# Schematics.net
KiCad netlist of a schematic drawn in Altium Designer
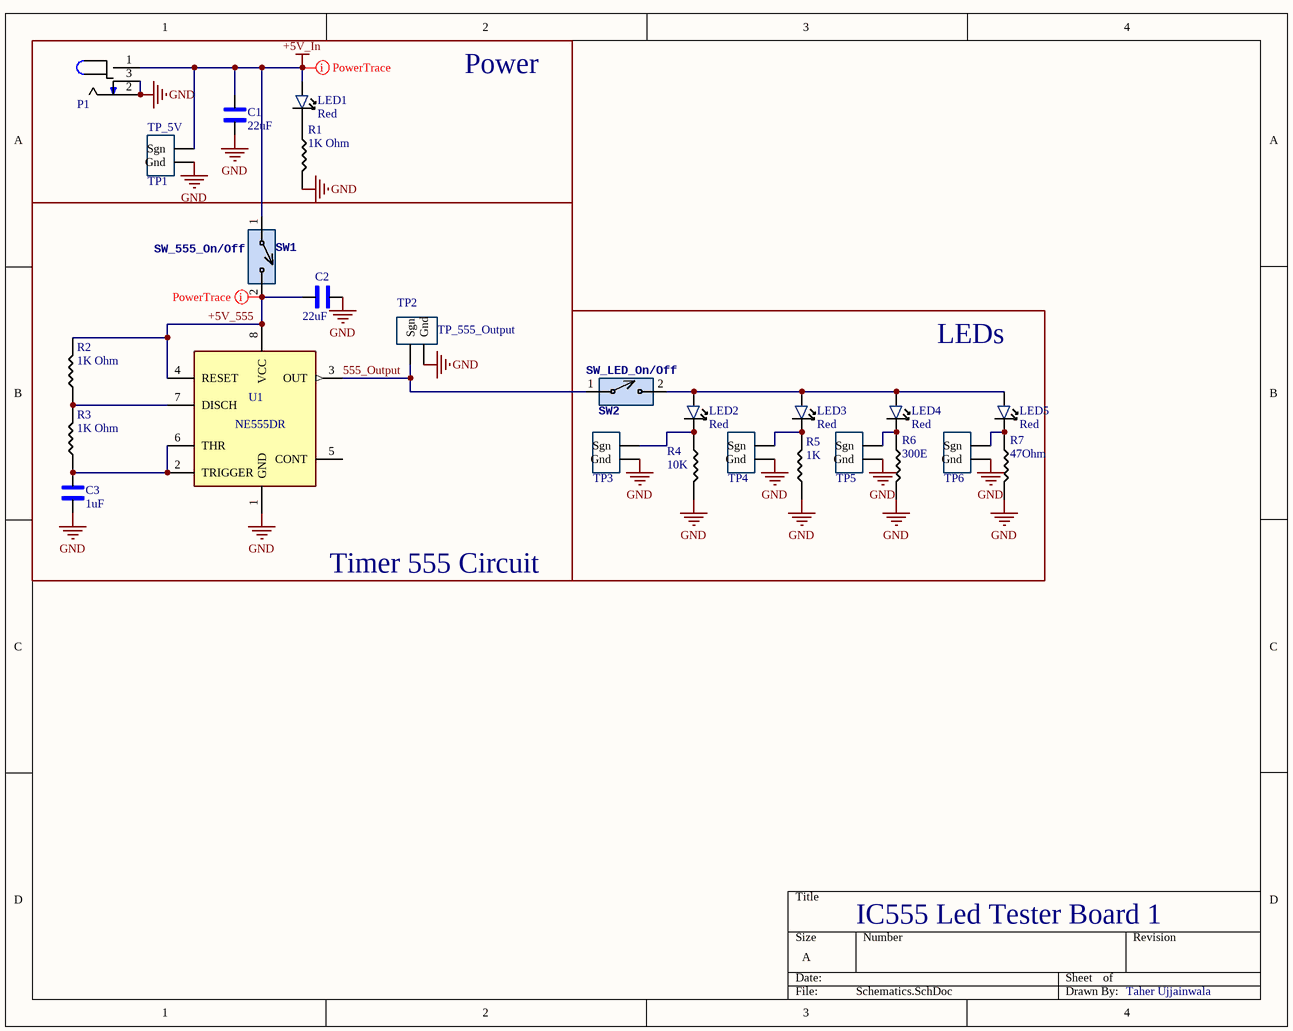
[diagram p0: Schematics.SchDoc]

(export (version "E")
  (design (tool "Eeschema 10.0.6"))
  (components
    (comp (ref "C1")
      (value "22uF")
      (footprint "1206_Passive_Capacitor")
      (description "22uF ±10% 25V X5R 1206 Multilayer Ceramic Capacitors MLCC - SMD/SMT RoHS")
      (fields (field (name "MFR PART #") "CL31A226KAHNNNE") (field (name "LCSC PART#") "C12891"))
      (libsource (lib "ECEN5730Lib_JLC_2021_08") (part "C_22uF_1206"))
    )
    (comp (ref "C2")
      (value "22uF")
      (footprint "1206_Passive_Capacitor")
      (description "22uF ±10% 25V X5R 1206 Multilayer Ceramic Capacitors MLCC - SMD/SMT RoHS")
      (fields (field (name "MFR PART #") "CL31A226KAHNNNE") (field (name "LCSC PART#") "C12891"))
      (libsource (lib "ECEN5730Lib_JLC_2021_08") (part "C_22uF_1206"))
    )
    (comp (ref "C3")
      (value "1uF")
      (footprint "1206_Passive_Capacitor")
      (description "MULTILAYER CERAMIC CAPACITORS MLCC - SMD/SMT 1UF 50V 1206 ROHS")
      (fields (field (name "DIGIKEY PART") "399-8150-1-ND") (field (name "MFR PART #") "CL31B105KBHNNNE"))
      (libsource (lib "ECEN5730Lib_JLC_2021_08") (part "C_1uF_1206"))
    )
    (comp (ref "LED1")
      (value "Red")
      (footprint "LED_1206")
      (description "Red 621~631nm 1206 Light Emitting Diodes (LED) RoHS")
      (fields (field (name "MFR PART #") "15-21/R6C-FQ1R1B/2T") (field (name "LCSC PART#") "C93133"))
      (libsource (lib "ECEN5730Lib_JLC_2021_08") (part "LED_RED_1206"))
    )
    (comp (ref "LED2")
      (value "Red")
      (footprint "LED_1206")
      (description "Red 621~631nm 1206 Light Emitting Diodes (LED) RoHS")
      (fields (field (name "MFR PART #") "15-21/R6C-FQ1R1B/2T") (field (name "LCSC PART#") "C93133"))
      (libsource (lib "ECEN5730Lib_JLC_2021_08") (part "LED_RED_1206"))
    )
    (comp (ref "LED3")
      (value "Red")
      (footprint "LED_1206")
      (description "Red 621~631nm 1206 Light Emitting Diodes (LED) RoHS")
      (fields (field (name "MFR PART #") "15-21/R6C-FQ1R1B/2T") (field (name "LCSC PART#") "C93133"))
      (libsource (lib "ECEN5730Lib_JLC_2021_08") (part "LED_RED_1206"))
    )
    (comp (ref "LED4")
      (value "Red")
      (footprint "LED_1206")
      (description "Red 621~631nm 1206 Light Emitting Diodes (LED) RoHS")
      (fields (field (name "MFR PART #") "15-21/R6C-FQ1R1B/2T") (field (name "LCSC PART#") "C93133"))
      (libsource (lib "ECEN5730Lib_JLC_2021_08") (part "LED_RED_1206"))
    )
    (comp (ref "LED5")
      (value "Red")
      (footprint "LED_1206")
      (description "Red 621~631nm 1206 Light Emitting Diodes (LED) RoHS")
      (fields (field (name "MFR PART #") "15-21/R6C-FQ1R1B/2T") (field (name "LCSC PART#") "C93133"))
      (libsource (lib "ECEN5730Lib_JLC_2021_08") (part "LED_RED_1206"))
    )
    (comp (ref "P1")
      (value "Power Jack")
      (footprint "Power_Jack")
      (description "Power Barrel Connector Jack 2.10mm ID (0.083\"), 5.50mm OD (0.217\") Through Hole, Right Angle")
      (fields (field (name "DIGIKEY PART") "CP-102A-ND") (field (name "LCSC PART#") "C136744"))
      (libsource (lib "ECEN5730Lib_JLC_2021_08") (part "P_Power Jack"))
    )
    (comp (ref "R1")
      (value "1K Ohm")
      (footprint "1206_Passive_Resitor")
      (description "CHIP RESISTOR - SURFACE MOUNT 1KOHMS ±1% 1/4W 1206 ROHS")
      (fields (field (name "DIGIKEY PART") "RNCP1206FTD1K00CT-ND") (field (name "LCSC PART#") "C4410"))
      (libsource (lib "ECEN5730Lib_JLC_2021_08") (part "R_1K_1206"))
    )
    (comp (ref "R2")
      (value "1K Ohm")
      (footprint "1206_Passive_Resitor")
      (description "CHIP RESISTOR - SURFACE MOUNT 1KOHMS ±1% 1/4W 1206 ROHS")
      (fields (field (name "DIGIKEY PART") "RNCP1206FTD1K00CT-ND") (field (name "LCSC PART#") "C4410"))
      (libsource (lib "ECEN5730Lib_JLC_2021_08") (part "R_1K_1206"))
    )
    (comp (ref "R3")
      (value "1K Ohm")
      (footprint "1206_Passive_Resitor")
      (description "CHIP RESISTOR - SURFACE MOUNT 1KOHMS ±1% 1/4W 1206 ROHS")
      (fields (field (name "DIGIKEY PART") "RNCP1206FTD1K00CT-ND") (field (name "LCSC PART#") "C4410"))
      (libsource (lib "ECEN5730Lib_JLC_2021_08") (part "R_1K_1206"))
    )
    (comp (ref "R4")
      (value "10K")
      (footprint "1206_Passive_Resitor")
      (description "10 kOhms ±5% 0.25W, 1/4W Chip Resistor 1206 (3216 Metric) Automotive AEC-Q200 Thick Film")
      (fields (field (name "DIGIKEY PART") "RMCF1206JT300RCT-ND") (field (name "LCSC PART#") "C17902"))
      (libsource (lib "ECEN5730Lib_JLC_2021_08") (part "R_10KOhm_1206"))
    )
    (comp (ref "R5")
      (value "1K")
      (footprint "1206_Passive_Resitor")
      (description "CHIP RESISTOR - SURFACE MOUNT 1KOHMS ±1% 1/4W 1206 ROHS")
      (fields (field (name "DIGIKEY PART") "RNCP1206FTD1K00CT-ND") (field (name "LCSC PART#") "C4410"))
      (libsource (lib "ECEN5730Lib_JLC_2021_08") (part "R_1K_1206"))
    )
    (comp (ref "R6")
      (value "300E")
      (footprint "1206_Passive_Resitor")
      (description "CHIP RESISTOR - SURFACE MOUNT 300OHMS ±1% 1/4W 1206 ROHS")
      (fields (field (name "MFR PART #") "1206W4F3000T5E") (field (name "LCSC PART#") "C17887"))
      (libsource (lib "ECEN5730Lib_JLC_2021_08") (part "R_300Ohm_1206"))
    )
    (comp (ref "R7")
      (value "47Ohm")
      (footprint "1206_Passive_Resitor")
      (description "47Ω ±5% 0.25W ±200ppm/℃ 1206 Chip Resistor - Surface Mount RoHS")
      (fields (field (name "MFR PART #") "1206W4J0470T5E") (field (name "LCSC PART#") "C25384"))
      (libsource (lib "ECEN5730Lib_JLC_2021_08") (part "R_47Ohm_1206"))
    )
    (comp (ref "SW1")
      (value "SW_555_On/Off")
      (footprint "2Pin-Header-Conn")
      (description "2Pin Header")
      (fields (field (name "LCSC PART#") "C124375"))
      (libsource (lib "ECEN5730Lib_JLC_2021_08") (part "SW_2Pin_100mil_Switch"))
    )
    (comp (ref "SW2")
      (value "SW_LED_On/Off")
      (footprint "2Pin-Header-Conn")
      (description "2Pin Header")
      (fields (field (name "LCSC PART#") "C124375"))
      (libsource (lib "") (part "SW_2Pin_100mil_Switch_1"))
    )
    (comp (ref "TP1")
      (value "TP_5V")
      (footprint "TP10x_Probe")
      (description "Test Point 300 mil centers")
      (libsource (lib "ECEN5730Lib_Manual_2021_08") (part "TP_10x_Probe"))
    )
    (comp (ref "TP2")
      (value "TP_555_Output")
      (footprint "TP10x_Probe")
      (description "Test Point 300 mil centers")
      (libsource (lib "") (part "TP_10x_Probe_1"))
    )
    (comp (ref "TP3")
      (value "10x Probe TP")
      (footprint "TP10x_Probe")
      (description "Test Point 300 mil centers")
      (libsource (lib "ECEN5730Lib_Manual_2021_08") (part "TP_10x_Probe"))
    )
    (comp (ref "TP4")
      (value "10x Probe TP")
      (footprint "TP10x_Probe")
      (description "Test Point 300 mil centers")
      (libsource (lib "ECEN5730Lib_Manual_2021_08") (part "TP_10x_Probe"))
    )
    (comp (ref "TP5")
      (value "10x Probe TP")
      (footprint "TP10x_Probe")
      (description "Test Point 300 mil centers")
      (libsource (lib "ECEN5730Lib_Manual_2021_08") (part "TP_10x_Probe"))
    )
    (comp (ref "TP6")
      (value "10x Probe TP")
      (footprint "TP10x_Probe")
      (description "Test Point 300 mil centers")
      (libsource (lib "ECEN5730Lib_Manual_2021_08") (part "TP_10x_Probe"))
    )
    (comp (ref "U1")
      (value "NE555DR")
      (footprint "TS555IDTTR")
      (description "555 Timer SOIC-8_150MIL ROHS 150ns Rise Time")
      (fields (field (name "LCSC PART#") "C7593"))
      (libsource (lib "ECEN5730Lib_JLC_2021_08") (part "U_555_Slow"))
    )
  )
  (nets
    (net (code "1") (name "+5V_In") (class "Default")
      (node (ref "C1") (pin "2") (pinfunction "2_2") (pintype "passive"))
      (node (ref "LED1") (pin "1") (pinfunction "1_1") (pintype "passive"))
      (node (ref "P1") (pin "1") (pinfunction "1_1") (pintype "power_in"))
      (node (ref "SW1") (pin "1") (pinfunction "1_1") (pintype "passive"))
      (node (ref "TP1") (pin "1") (pinfunction "Sgn_1") (pintype "passive"))
    )
    (net (code "2") (name "/+5V_555") (class "Default")
      (node (ref "C2") (pin "2") (pinfunction "2_2") (pintype "passive"))
      (node (ref "R2") (pin "2") (pinfunction "2_2") (pintype "passive"))
      (node (ref "SW1") (pin "2") (pinfunction "2_2") (pintype "passive"))
      (node (ref "U1") (pin "4") (pinfunction "RESET_4") (pintype "passive"))
      (node (ref "U1") (pin "8") (pinfunction "VCC_8") (pintype "power_in"))
    )
    (net (code "3") (name "/555_Output") (class "Default")
      (node (ref "SW2") (pin "1") (pinfunction "1_1") (pintype "passive"))
      (node (ref "TP2") (pin "1") (pinfunction "Sgn_1") (pintype "passive"))
      (node (ref "U1") (pin "3") (pinfunction "OUT_3") (pintype "output"))
    )
    (net (code "4") (name "GND") (class "Default")
      (node (ref "C1") (pin "1") (pinfunction "1_1") (pintype "passive"))
      (node (ref "C2") (pin "1") (pinfunction "1_1") (pintype "passive"))
      (node (ref "C3") (pin "1") (pinfunction "1_1") (pintype "passive"))
      (node (ref "P1") (pin "2") (pinfunction "2_2") (pintype "power_in"))
      (node (ref "P1") (pin "3") (pinfunction "3_3") (pintype "power_in"))
      (node (ref "R1") (pin "2") (pinfunction "2_2") (pintype "passive"))
      (node (ref "R4") (pin "2") (pinfunction "2_2") (pintype "passive"))
      (node (ref "R5") (pin "1") (pinfunction "1_1") (pintype "passive"))
      (node (ref "R6") (pin "2") (pinfunction "2_2") (pintype "passive"))
      (node (ref "R7") (pin "2") (pinfunction "2_2") (pintype "passive"))
      (node (ref "TP1") (pin "2") (pinfunction "Gnd_2") (pintype "passive"))
      (node (ref "TP2") (pin "2") (pinfunction "Gnd_2") (pintype "passive"))
      (node (ref "TP3") (pin "2") (pinfunction "Gnd_2") (pintype "passive"))
      (node (ref "TP4") (pin "2") (pinfunction "Gnd_2") (pintype "passive"))
      (node (ref "TP5") (pin "2") (pinfunction "Gnd_2") (pintype "passive"))
      (node (ref "TP6") (pin "2") (pinfunction "Gnd_2") (pintype "passive"))
      (node (ref "U1") (pin "1") (pinfunction "GND_1") (pintype "power_in"))
    )
    (net (code "5") (name "Net-(LED1-Pad2)") (class "Default")
      (node (ref "LED1") (pin "2") (pinfunction "2_2") (pintype "passive"))
      (node (ref "R1") (pin "1") (pinfunction "1_1") (pintype "passive"))
    )
    (net (code "6") (name "Net-(LED2-Pad1)") (class "Default")
      (node (ref "LED2") (pin "1") (pinfunction "1_1") (pintype "passive"))
      (node (ref "LED3") (pin "1") (pinfunction "1_1") (pintype "passive"))
      (node (ref "LED4") (pin "1") (pinfunction "1_1") (pintype "passive"))
      (node (ref "LED5") (pin "1") (pinfunction "1_1") (pintype "passive"))
      (node (ref "SW2") (pin "2") (pinfunction "2_2") (pintype "passive"))
    )
    (net (code "7") (name "Net-(TP3-Sgn)") (class "Default")
      (node (ref "LED2") (pin "2") (pinfunction "2_2") (pintype "passive"))
      (node (ref "R4") (pin "1") (pinfunction "1_1") (pintype "passive"))
      (node (ref "TP3") (pin "1") (pinfunction "Sgn_1") (pintype "passive"))
    )
    (net (code "8") (name "Net-(TP4-Sgn)") (class "Default")
      (node (ref "LED3") (pin "2") (pinfunction "2_2") (pintype "passive"))
      (node (ref "R5") (pin "2") (pinfunction "2_2") (pintype "passive"))
      (node (ref "TP4") (pin "1") (pinfunction "Sgn_1") (pintype "passive"))
    )
    (net (code "9") (name "Net-(TP5-Sgn)") (class "Default")
      (node (ref "LED4") (pin "2") (pinfunction "2_2") (pintype "passive"))
      (node (ref "R6") (pin "1") (pinfunction "1_1") (pintype "passive"))
      (node (ref "TP5") (pin "1") (pinfunction "Sgn_1") (pintype "passive"))
    )
    (net (code "10") (name "Net-(TP6-Sgn)") (class "Default")
      (node (ref "LED5") (pin "2") (pinfunction "2_2") (pintype "passive"))
      (node (ref "R7") (pin "1") (pinfunction "1_1") (pintype "passive"))
      (node (ref "TP6") (pin "1") (pinfunction "Sgn_1") (pintype "passive"))
    )
    (net (code "11") (name "Net-(U1-DISCH)") (class "Default")
      (node (ref "R2") (pin "1") (pinfunction "1_1") (pintype "passive"))
      (node (ref "R3") (pin "2") (pinfunction "2_2") (pintype "passive"))
      (node (ref "U1") (pin "7") (pinfunction "DISCH_7") (pintype "passive"))
    )
    (net (code "12") (name "Net-(U1-THR)") (class "Default")
      (node (ref "C3") (pin "2") (pinfunction "2_2") (pintype "passive"))
      (node (ref "R3") (pin "1") (pinfunction "1_1") (pintype "passive"))
      (node (ref "U1") (pin "2") (pinfunction "TRIGGER_2") (pintype "passive"))
      (node (ref "U1") (pin "6") (pinfunction "THR_6") (pintype "passive"))
    )
    (net (code "13") (name "unconnected-(U1-CONT-Pad5)") (class "Default")
      (node (ref "U1") (pin "5") (pinfunction "CONT_5") (pintype "passive"))
    )
  )
)
